# SCH_5G23__2022-10-08.net
KiCad netlist of a schematic drawn in EasyEDA
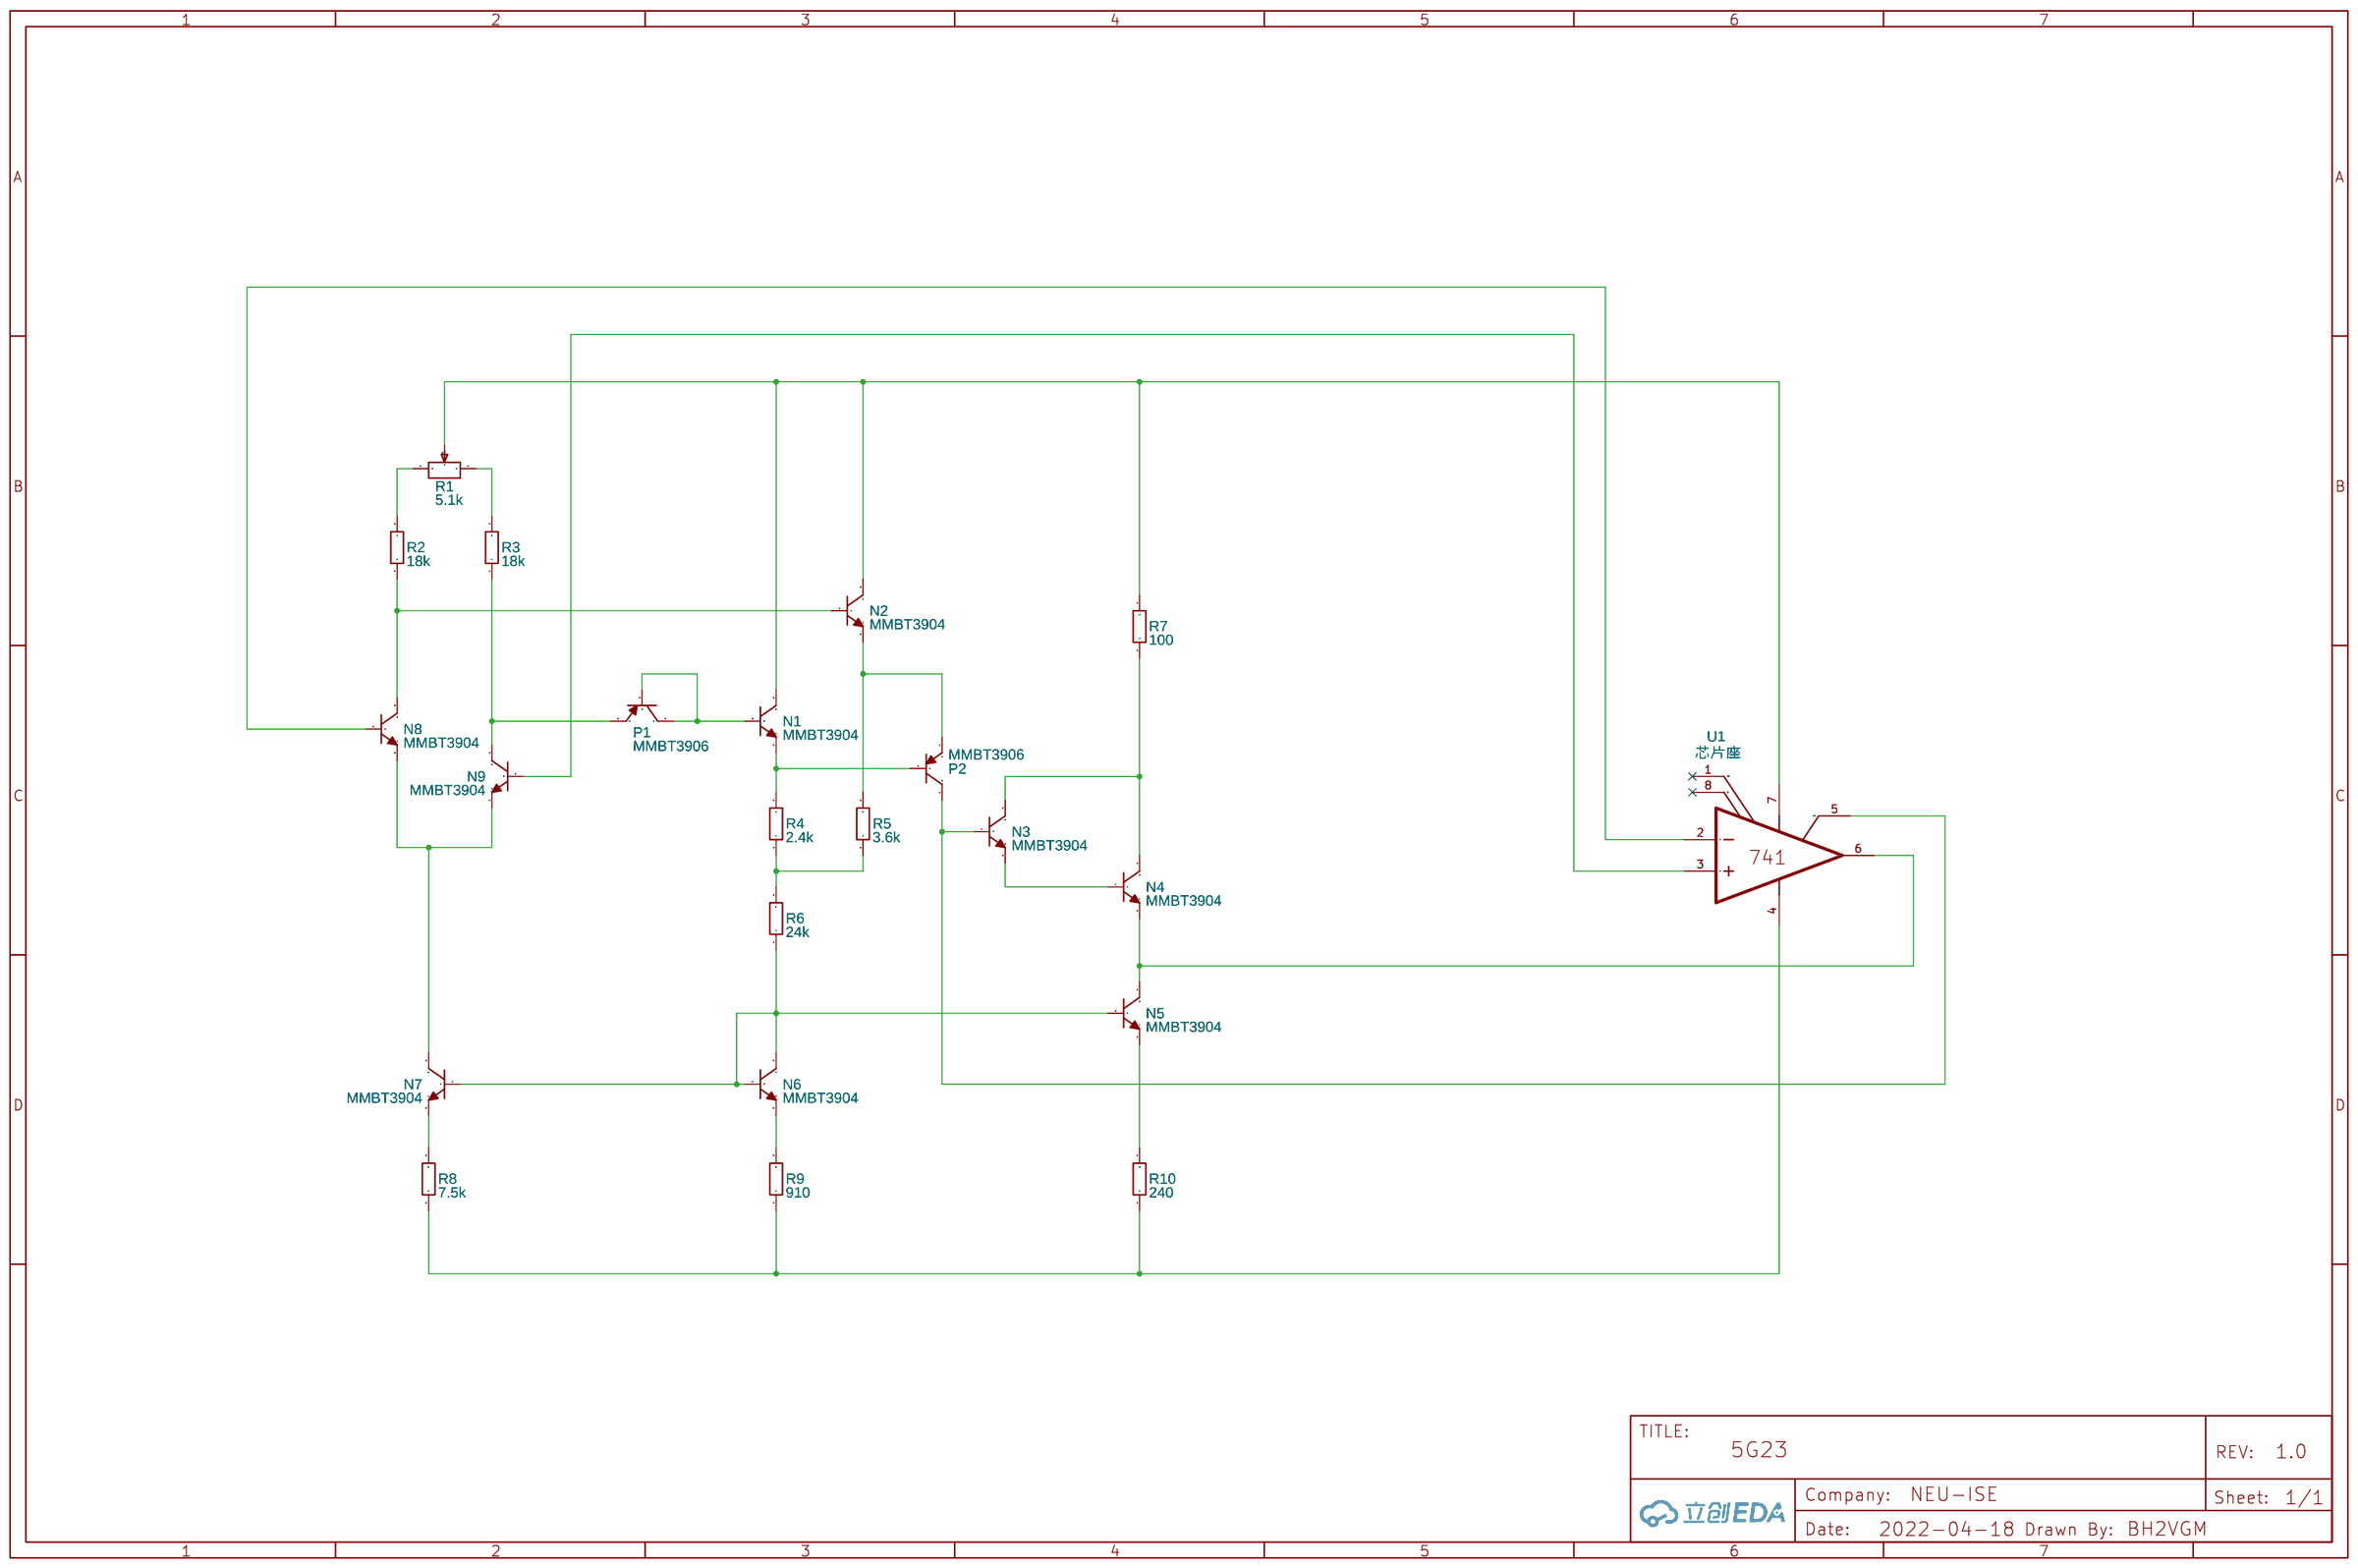
[diagram p0: schematic sheet]

(export (version "E")
  (design (tool "Eeschema 10.0.6"))
  (components
    (comp (ref "N1")
      (value "MMBT3904")
      (fields (field (name "BOM_Supplier Part") "C20526"))
      (libsource (lib "") (part "MMBT3904-C20526_1"))
    )
    (comp (ref "N2")
      (value "MMBT3904")
      (fields (field (name "BOM_Supplier Part") "C20526"))
      (libsource (lib "") (part "MMBT3904-C20526_1"))
    )
    (comp (ref "N3")
      (value "MMBT3904")
      (fields (field (name "BOM_Supplier Part") "C20526"))
      (libsource (lib "") (part "MMBT3904-C20526_1"))
    )
    (comp (ref "N4")
      (value "MMBT3904")
      (fields (field (name "BOM_Supplier Part") "C20526"))
      (libsource (lib "") (part "MMBT3904-C20526_1"))
    )
    (comp (ref "N5")
      (value "MMBT3904")
      (fields (field (name "BOM_Supplier Part") "C20526"))
      (libsource (lib "") (part "MMBT3904-C20526_1"))
    )
    (comp (ref "N6")
      (value "MMBT3904")
      (fields (field (name "BOM_Supplier Part") "C20526"))
      (libsource (lib "") (part "MMBT3904-C20526_1"))
    )
    (comp (ref "N7")
      (value "MMBT3904")
      (fields (field (name "BOM_Supplier Part") "C20526"))
      (libsource (lib "") (part "MMBT3904-C20526"))
    )
    (comp (ref "N8")
      (value "MMBT3904")
      (fields (field (name "BOM_Supplier Part") "C20526"))
      (libsource (lib "") (part "MMBT3904-C20526_1"))
    )
    (comp (ref "N9")
      (value "MMBT3904")
      (fields (field (name "BOM_Supplier Part") "C20526"))
      (libsource (lib "") (part "MMBT3904-C20526"))
    )
    (comp (ref "P1")
      (value "MMBT3906")
      (fields
        (field (name "BOM_Manufacturer Part") "MMBT3906G-AE3-R")
        (field (name "BOM_Supplier Part") "C87445")
      )
      (libsource (lib "") (part "MMBT3906G-AE3-R"))
    )
    (comp (ref "P2")
      (value "MMBT3906")
      (fields
        (field (name "BOM_Manufacturer Part") "MMBT3906G-AE3-R")
        (field (name "BOM_Supplier Part") "C87445")
      )
      (libsource (lib "") (part "MMBT3906G-AE3-R_1"))
    )
    (comp (ref "R1")
      (value "5.1k")
      (fields
        (field (name "BOM_Manufacturer Part") "VG039NCHXTB204")
        (field (name "BOM_Supplier Part") "C128551")
      )
      (libsource (lib "") (part "VG039NCHXTB204"))
    )
    (comp (ref "R2")
      (value "18k")
      (fields (field (name "BOM_Manufacturer Part") "0805") (field (name "BOM_Supplier Part") "C9900012715"))
      (libsource (lib "") (part "0805"))
    )
    (comp (ref "R3")
      (value "18k")
      (fields (field (name "BOM_Manufacturer Part") "0805") (field (name "BOM_Supplier Part") "C9900012715"))
      (libsource (lib "") (part "0805"))
    )
    (comp (ref "R4")
      (value "2.4k")
      (fields (field (name "BOM_Manufacturer Part") "0805") (field (name "BOM_Supplier Part") "C9900012715"))
      (libsource (lib "") (part "0805"))
    )
    (comp (ref "R5")
      (value "3.6k")
      (fields (field (name "BOM_Manufacturer Part") "0805") (field (name "BOM_Supplier Part") "C9900012715"))
      (libsource (lib "") (part "0805"))
    )
    (comp (ref "R6")
      (value "24k")
      (fields (field (name "BOM_Manufacturer Part") "0805") (field (name "BOM_Supplier Part") "C9900012715"))
      (libsource (lib "") (part "0805"))
    )
    (comp (ref "R7")
      (value "100")
      (fields (field (name "BOM_Manufacturer Part") "0805") (field (name "BOM_Supplier Part") "C9900012715"))
      (libsource (lib "") (part "0805"))
    )
    (comp (ref "R8")
      (value "7.5k")
      (fields (field (name "BOM_Manufacturer Part") "0805") (field (name "BOM_Supplier Part") "C9900012715"))
      (libsource (lib "") (part "0805"))
    )
    (comp (ref "R9")
      (value "910")
      (fields (field (name "BOM_Manufacturer Part") "0805") (field (name "BOM_Supplier Part") "C9900012715"))
      (libsource (lib "") (part "0805"))
    )
    (comp (ref "R10")
      (value "240")
      (fields (field (name "BOM_Manufacturer Part") "0805") (field (name "BOM_Supplier Part") "C9900012715"))
      (libsource (lib "") (part "0805"))
    )
    (comp (ref "U1")
      (value "芯片座")
      (fields (field (name "BOM_Manufacturer Part") "UA741CDR") (field (name "BOM_Supplier Part") "C2057458"))
      (libsource (lib "") (part "UA741CP"))
    )
  )
  (nets
    (net (code "1") (name "Net-(N1-B)") (class "Default")
      (node (ref "N1") (pin "1") (pinfunction "B_1") (pintype "unspecified"))
      (node (ref "P1") (pin "2") (pinfunction "B_2") (pintype "input"))
      (node (ref "P1") (pin "3") (pinfunction "C_3") (pintype "input"))
    )
    (net (code "2") (name "Net-(N1-C)") (class "Default")
      (node (ref "N1") (pin "3") (pinfunction "C_3") (pintype "unspecified"))
      (node (ref "N2") (pin "3") (pinfunction "C_3") (pintype "unspecified"))
      (node (ref "R1") (pin "2") (pinfunction "2_2") (pintype "input"))
      (node (ref "R7") (pin "2") (pinfunction "2_2") (pintype "unspecified"))
      (node (ref "U1") (pin "7") (pinfunction "VCC+_7") (pintype "passive"))
    )
    (net (code "3") (name "Net-(N1-E)") (class "Default")
      (node (ref "N1") (pin "2") (pinfunction "E_2") (pintype "unspecified"))
      (node (ref "P2") (pin "2") (pinfunction "B_2") (pintype "input"))
      (node (ref "R4") (pin "2") (pinfunction "2_2") (pintype "unspecified"))
    )
    (net (code "4") (name "Net-(N2-B)") (class "Default")
      (node (ref "N2") (pin "1") (pinfunction "B_1") (pintype "unspecified"))
      (node (ref "N8") (pin "3") (pinfunction "C_3") (pintype "unspecified"))
      (node (ref "R2") (pin "1") (pinfunction "1_1") (pintype "unspecified"))
    )
    (net (code "5") (name "Net-(N2-E)") (class "Default")
      (node (ref "N2") (pin "2") (pinfunction "E_2") (pintype "unspecified"))
      (node (ref "P2") (pin "1") (pinfunction "E_1") (pintype "input"))
      (node (ref "R5") (pin "2") (pinfunction "2_2") (pintype "unspecified"))
    )
    (net (code "6") (name "Net-(N3-B)") (class "Default")
      (node (ref "N3") (pin "1") (pinfunction "B_1") (pintype "unspecified"))
      (node (ref "P2") (pin "3") (pinfunction "C_3") (pintype "input"))
      (node (ref "U1") (pin "5") (pinfunction "OFFSET_N2_5") (pintype "unspecified"))
    )
    (net (code "7") (name "Net-(N3-C)") (class "Default")
      (node (ref "N3") (pin "3") (pinfunction "C_3") (pintype "unspecified"))
      (node (ref "N4") (pin "3") (pinfunction "C_3") (pintype "unspecified"))
      (node (ref "R7") (pin "1") (pinfunction "1_1") (pintype "unspecified"))
    )
    (net (code "8") (name "Net-(N3-E)") (class "Default")
      (node (ref "N3") (pin "2") (pinfunction "E_2") (pintype "unspecified"))
      (node (ref "N4") (pin "1") (pinfunction "B_1") (pintype "unspecified"))
    )
    (net (code "9") (name "Net-(N4-E)") (class "Default")
      (node (ref "N4") (pin "2") (pinfunction "E_2") (pintype "unspecified"))
      (node (ref "N5") (pin "3") (pinfunction "C_3") (pintype "unspecified"))
      (node (ref "U1") (pin "6") (pinfunction "OUT_6") (pintype "output"))
    )
    (net (code "10") (name "Net-(N5-B)") (class "Default")
      (node (ref "N5") (pin "1") (pinfunction "B_1") (pintype "unspecified"))
      (node (ref "N6") (pin "1") (pinfunction "B_1") (pintype "unspecified"))
      (node (ref "N6") (pin "3") (pinfunction "C_3") (pintype "unspecified"))
      (node (ref "N7") (pin "1") (pinfunction "B_1") (pintype "unspecified"))
      (node (ref "R6") (pin "1") (pinfunction "1_1") (pintype "unspecified"))
    )
    (net (code "11") (name "Net-(N5-E)") (class "Default")
      (node (ref "N5") (pin "2") (pinfunction "E_2") (pintype "unspecified"))
      (node (ref "R10") (pin "2") (pinfunction "2_2") (pintype "unspecified"))
    )
    (net (code "12") (name "Net-(N6-E)") (class "Default")
      (node (ref "N6") (pin "2") (pinfunction "E_2") (pintype "unspecified"))
      (node (ref "R9") (pin "2") (pinfunction "2_2") (pintype "unspecified"))
    )
    (net (code "13") (name "Net-(N7-C)") (class "Default")
      (node (ref "N7") (pin "3") (pinfunction "C_3") (pintype "unspecified"))
      (node (ref "N8") (pin "2") (pinfunction "E_2") (pintype "unspecified"))
      (node (ref "N9") (pin "2") (pinfunction "E_2") (pintype "unspecified"))
    )
    (net (code "14") (name "Net-(N7-E)") (class "Default")
      (node (ref "N7") (pin "2") (pinfunction "E_2") (pintype "unspecified"))
      (node (ref "R8") (pin "2") (pinfunction "2_2") (pintype "unspecified"))
    )
    (net (code "15") (name "Net-(N8-B)") (class "Default")
      (node (ref "N8") (pin "1") (pinfunction "B_1") (pintype "unspecified"))
      (node (ref "U1") (pin "2") (pinfunction "-IN_2") (pintype "unspecified"))
    )
    (net (code "16") (name "Net-(N9-B)") (class "Default")
      (node (ref "N9") (pin "1") (pinfunction "B_1") (pintype "unspecified"))
      (node (ref "U1") (pin "3") (pinfunction "+IN_3") (pintype "unspecified"))
    )
    (net (code "17") (name "Net-(N9-C)") (class "Default")
      (node (ref "N9") (pin "3") (pinfunction "C_3") (pintype "unspecified"))
      (node (ref "P1") (pin "1") (pinfunction "E_1") (pintype "input"))
      (node (ref "R3") (pin "1") (pinfunction "1_1") (pintype "unspecified"))
    )
    (net (code "18") (name "Net-(R1-Pad1)") (class "Default")
      (node (ref "R1") (pin "1") (pinfunction "1_1") (pintype "input"))
      (node (ref "R2") (pin "2") (pinfunction "2_2") (pintype "unspecified"))
    )
    (net (code "19") (name "Net-(R1-Pad3)") (class "Default")
      (node (ref "R1") (pin "3") (pinfunction "3_3") (pintype "input"))
      (node (ref "R3") (pin "2") (pinfunction "2_2") (pintype "unspecified"))
    )
    (net (code "20") (name "Net-(R4-Pad1)") (class "Default")
      (node (ref "R4") (pin "1") (pinfunction "1_1") (pintype "unspecified"))
      (node (ref "R5") (pin "1") (pinfunction "1_1") (pintype "unspecified"))
      (node (ref "R6") (pin "2") (pinfunction "2_2") (pintype "unspecified"))
    )
    (net (code "21") (name "Net-(U1-VCC-)") (class "Default")
      (node (ref "R10") (pin "1") (pinfunction "1_1") (pintype "unspecified"))
      (node (ref "R8") (pin "1") (pinfunction "1_1") (pintype "unspecified"))
      (node (ref "R9") (pin "1") (pinfunction "1_1") (pintype "unspecified"))
      (node (ref "U1") (pin "4") (pinfunction "VCC-_4") (pintype "passive"))
    )
    (net (code "22") (name "unconnected-(U1-NC-Pad8)") (class "Default")
      (node (ref "U1") (pin "8") (pinfunction "NC_8") (pintype "unspecified+no_connect"))
    )
    (net (code "23") (name "unconnected-(U1-OFFSET_N1-Pad1)") (class "Default")
      (node (ref "U1") (pin "1") (pinfunction "OFFSET_N1_1") (pintype "unspecified+no_connect"))
    )
  )
)
